# OLM-base_v0_9.net
KiCad netlist of a schematic drawn in EAGLE
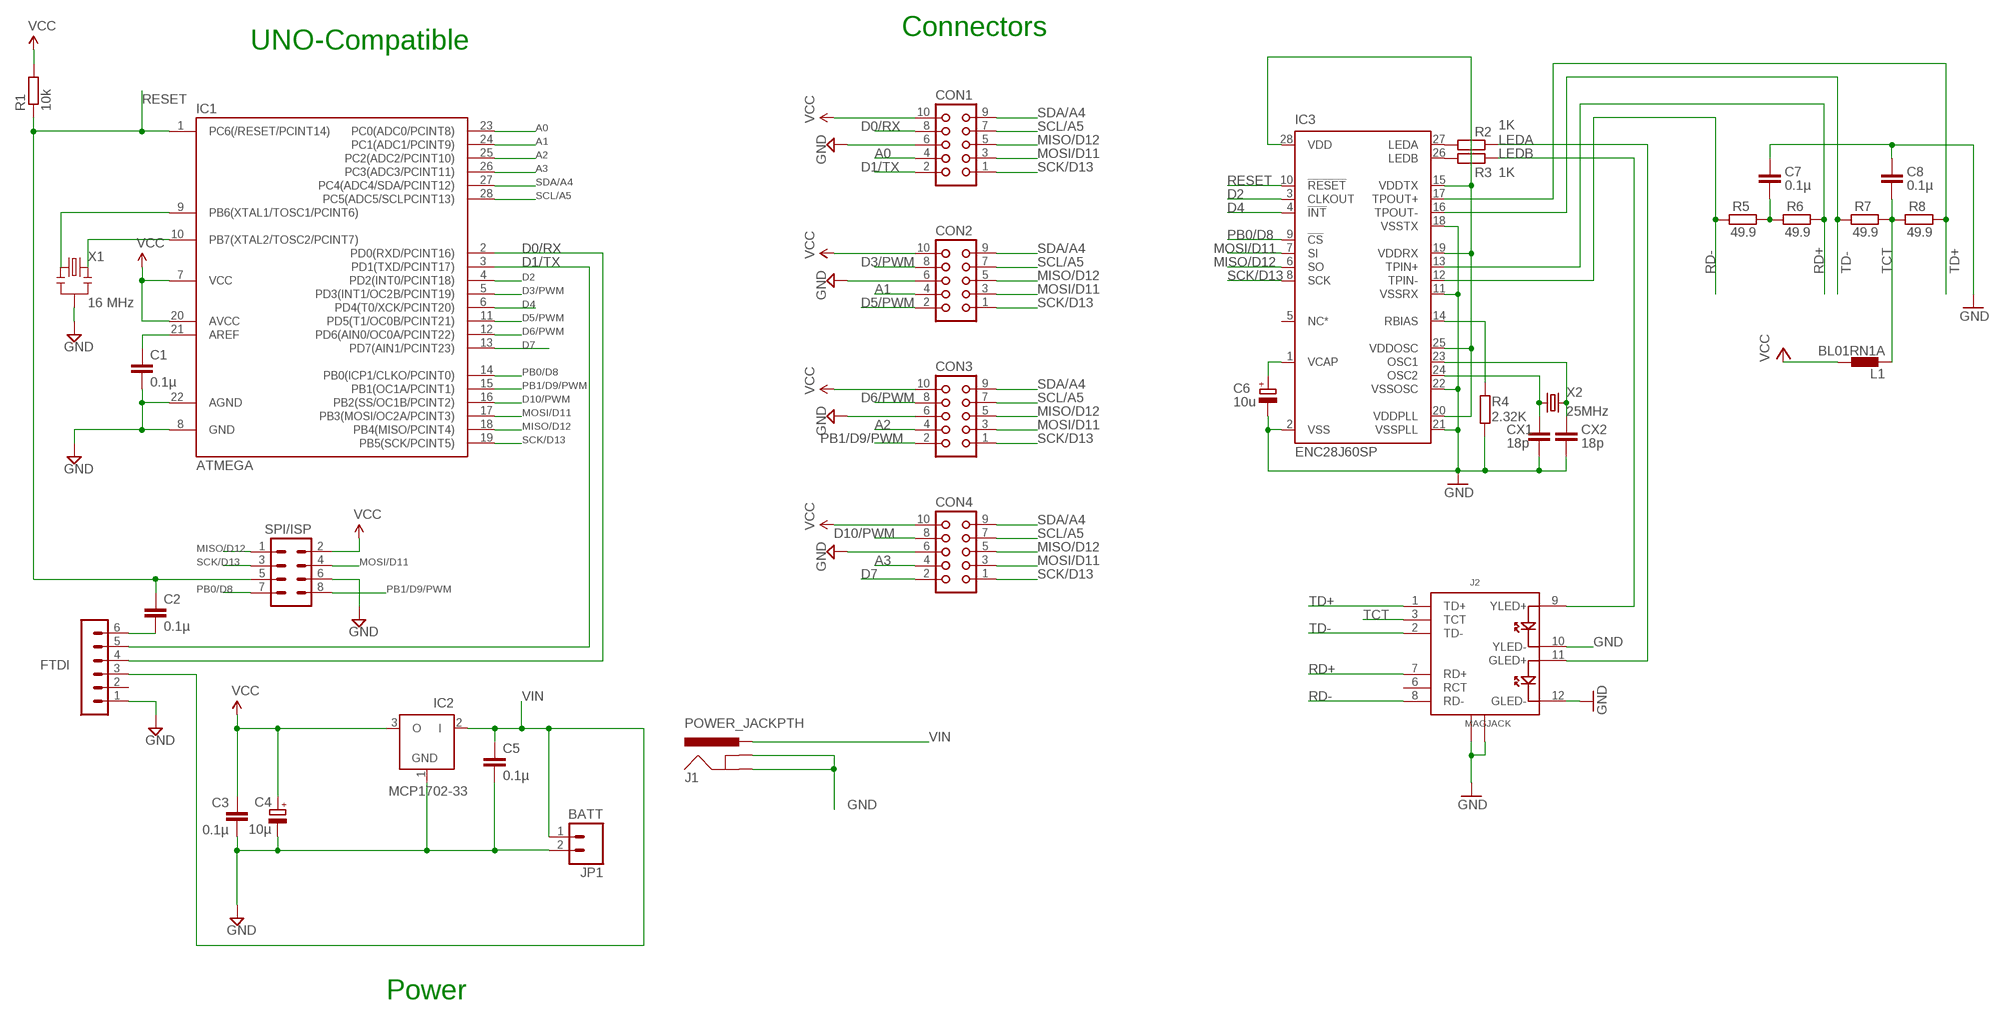
[diagram p0: schematic, sheet 1]

(export (version "E")
  (design (tool "Eeschema 10.0.6"))
  (components
    (comp (ref "C1")
      (value "0.1µ")
      (footprint "eagle-import:C025-024X044")
      (libsource (lib "eagle-import") (part "C-EU025-024X044"))
    )
    (comp (ref "C2")
      (value "0.1µ")
      (footprint "eagle-import:C025-024X044")
      (libsource (lib "eagle-import") (part "C-EU025-024X044"))
    )
    (comp (ref "C3")
      (value "0.1µ")
      (footprint "eagle-import:C025-024X044")
      (libsource (lib "eagle-import") (part "C-EU025-024X044"))
    )
    (comp (ref "C4")
      (value "10µ")
      (footprint "eagle-import:E1,8-4")
      (libsource (lib "eagle-import") (part "CPOL-EUE1.8-4"))
    )
    (comp (ref "C5")
      (value "0.1µ")
      (footprint "eagle-import:C025-024X044")
      (libsource (lib "eagle-import") (part "C-EU025-024X044"))
    )
    (comp (ref "C6")
      (value "10u")
      (footprint "eagle-import:E1,8-4")
      (libsource (lib "eagle-import") (part "CPOL-EUE1.8-4"))
    )
    (comp (ref "C7")
      (value "0.1µ")
      (footprint "eagle-import:C025-024X044")
      (libsource (lib "eagle-import") (part "C-EU025-024X044"))
    )
    (comp (ref "C8")
      (value "0.1µ")
      (footprint "eagle-import:C025-024X044")
      (libsource (lib "eagle-import") (part "C-EU025-024X044"))
    )
    (comp (ref "CON1")
      (value "CON10L")
      (footprint "eagle-import:CON10L")
      (libsource (lib "eagle-import") (part "CON10L"))
    )
    (comp (ref "CON2")
      (value "CON10L")
      (footprint "eagle-import:CON10L")
      (libsource (lib "eagle-import") (part "CON10L"))
    )
    (comp (ref "CON3")
      (value "CON10L")
      (footprint "eagle-import:CON10L")
      (libsource (lib "eagle-import") (part "CON10L"))
    )
    (comp (ref "CON4")
      (value "CON10L")
      (footprint "eagle-import:CON10L")
      (libsource (lib "eagle-import") (part "CON10L"))
    )
    (comp (ref "CX1")
      (value "18p")
      (footprint "eagle-import:C025-024X044")
      (libsource (lib "eagle-import") (part "C-EU025-024X044"))
    )
    (comp (ref "CX2")
      (value "18p")
      (footprint "eagle-import:C025-024X044")
      (libsource (lib "eagle-import") (part "C-EU025-024X044"))
    )
    (comp (ref "FTDI")
      (value "FTDI")
      (footprint "eagle-import:MA06-1")
      (libsource (lib "eagle-import") (part "MA06-1"))
    )
    (comp (ref "IC1")
      (value "ATMEGA")
      (footprint "eagle-import:DIL28-3")
      (libsource (lib "eagle-import") (part "ATMEGA48/88/168-PU"))
    )
    (comp (ref "IC2")
      (value "MCP1702-33")
      (footprint "eagle-import:TO92")
      (libsource (lib "eagle-import") (part "MCP1702Z"))
    )
    (comp (ref "IC3")
      (value "ENC28J60SP")
      (footprint "eagle-import:DIL28-3")
      (fields (field (name "MF") "MICROCHIP") (field (name "MPN") "ENC28J60/SP"))
      (libsource (lib "eagle-import") (part "ENC28J60SP"))
    )
    (comp (ref "J1")
      (value "POWER_JACKPTH")
      (footprint "eagle-import:POWER_JACK_PTH")
      (libsource (lib "eagle-import") (part "POWER_JACKPTH"))
    )
    (comp (ref "J2")
      (value "MAGJACK")
      (footprint "eagle-import:MAGJACK")
      (libsource (lib "eagle-import") (part "MAGJACK"))
    )
    (comp (ref "JP1")
      (value "BATT")
      (footprint "eagle-import:1X02_LOCK_LONGPADS")
      (libsource (lib "eagle-import") (part "M02LOCK_LONGPADS"))
    )
    (comp (ref "L1")
      (value "BL01RN1A")
      (footprint "eagle-import:BL01RN1A")
      (libsource (lib "eagle-import") (part "BL01RN1A"))
    )
    (comp (ref "R1")
      (value "10k")
      (footprint "eagle-import:0204_7")
      (libsource (lib "eagle-import") (part "resistor_R-EU_0204/7"))
    )
    (comp (ref "R2")
      (value "1K")
      (footprint "eagle-import:0204_7")
      (libsource (lib "eagle-import") (part "R-EU_0204/7"))
    )
    (comp (ref "R3")
      (value "1K")
      (footprint "eagle-import:0204_7")
      (libsource (lib "eagle-import") (part "R-EU_0204/7"))
    )
    (comp (ref "R4")
      (value "2.32K")
      (footprint "eagle-import:0204_7")
      (libsource (lib "eagle-import") (part "R-EU_0204/7"))
    )
    (comp (ref "R5")
      (value "49.9")
      (footprint "eagle-import:0204_7")
      (libsource (lib "eagle-import") (part "R-EU_0204/7"))
    )
    (comp (ref "R6")
      (value "49.9")
      (footprint "eagle-import:0204_7")
      (libsource (lib "eagle-import") (part "R-EU_0204/7"))
    )
    (comp (ref "R7")
      (value "49.9")
      (footprint "eagle-import:0204_7")
      (libsource (lib "eagle-import") (part "R-EU_0204/7"))
    )
    (comp (ref "R8")
      (value "49.9")
      (footprint "eagle-import:0204_7")
      (libsource (lib "eagle-import") (part "R-EU_0204/7"))
    )
    (comp (ref "SV1")
      (value "SPI/ISP")
      (footprint "eagle-import:MA04-2")
      (libsource (lib "eagle-import") (part "MA04-2"))
    )
    (comp (ref "X1")
      (value "16 MHz")
      (footprint "eagle-import:RESONATOR-PTH")
      (libsource (lib "eagle-import") (part "RESONATORPTH"))
    )
    (comp (ref "X2")
      (value "25MHz")
      (footprint "eagle-import:HC49US")
      (libsource (lib "eagle-import") (part "CRYSTALHC49US"))
    )
  )
  (nets
    (net (code "1") (name "/A0") (class "Default")
      (node (ref "CON1") (pin "4") (pinfunction "4_4") (pintype "passive"))
      (node (ref "IC1") (pin "23") (pinfunction "PC0(ADC0/PCINT8)_23") (pintype "bidirectional"))
    )
    (net (code "2") (name "/A1") (class "Default")
      (node (ref "CON2") (pin "4") (pinfunction "4_4") (pintype "passive"))
      (node (ref "IC1") (pin "24") (pinfunction "PC1(ADC1/PCINT9)_24") (pintype "bidirectional"))
    )
    (net (code "3") (name "/A2") (class "Default")
      (node (ref "CON3") (pin "4") (pinfunction "4_4") (pintype "passive"))
      (node (ref "IC1") (pin "25") (pinfunction "PC2(ADC2/PCINT10)_25") (pintype "bidirectional"))
    )
    (net (code "4") (name "/A3") (class "Default")
      (node (ref "CON4") (pin "4") (pinfunction "4_4") (pintype "passive"))
      (node (ref "IC1") (pin "26") (pinfunction "PC3(ADC3/PCINT11)_26") (pintype "bidirectional"))
    )
    (net (code "5") (name "/D0{slash}RX") (class "Default")
      (node (ref "CON1") (pin "8") (pinfunction "8_8") (pintype "passive"))
      (node (ref "FTDI") (pin "4") (pinfunction "4_4") (pintype "passive"))
      (node (ref "IC1") (pin "2") (pinfunction "PD0(RXD/PCINT16)_2") (pintype "bidirectional"))
    )
    (net (code "6") (name "/D1{slash}TX") (class "Default")
      (node (ref "CON1") (pin "2") (pinfunction "2_2") (pintype "passive"))
      (node (ref "FTDI") (pin "5") (pinfunction "5_5") (pintype "passive"))
      (node (ref "IC1") (pin "3") (pinfunction "PD1(TXD/PCINT17)_3") (pintype "bidirectional"))
    )
    (net (code "7") (name "/D2") (class "Default")
      (node (ref "IC1") (pin "4") (pinfunction "PD2(INT0/PCINT18)_4") (pintype "bidirectional"))
      (node (ref "IC3") (pin "3") (pinfunction "CLKOUT_3") (pintype "output"))
    )
    (net (code "8") (name "/D3{slash}PWM") (class "Default")
      (node (ref "CON2") (pin "8") (pinfunction "8_8") (pintype "passive"))
      (node (ref "IC1") (pin "5") (pinfunction "PD3(INT1/OC2B/PCINT19)_5") (pintype "bidirectional"))
    )
    (net (code "9") (name "/D4") (class "Default")
      (node (ref "IC1") (pin "6") (pinfunction "PD4(T0/XCK/PCINT20)_6") (pintype "bidirectional"))
      (node (ref "IC3") (pin "4") (pinfunction "~{INT}_4") (pintype "output"))
    )
    (net (code "10") (name "/D5{slash}PWM") (class "Default")
      (node (ref "CON2") (pin "2") (pinfunction "2_2") (pintype "passive"))
      (node (ref "IC1") (pin "11") (pinfunction "PD5(T1/OC0B/PCINT21)_11") (pintype "bidirectional"))
    )
    (net (code "11") (name "/D6{slash}PWM") (class "Default")
      (node (ref "CON3") (pin "8") (pinfunction "8_8") (pintype "passive"))
      (node (ref "IC1") (pin "12") (pinfunction "PD6(AIN0/OC0A/PCINT22)_12") (pintype "bidirectional"))
    )
    (net (code "12") (name "/D7") (class "Default")
      (node (ref "CON4") (pin "2") (pinfunction "2_2") (pintype "passive"))
      (node (ref "IC1") (pin "13") (pinfunction "PD7(AIN1/PCINT23)_13") (pintype "bidirectional"))
    )
    (net (code "13") (name "/D10{slash}PWM") (class "Default")
      (node (ref "CON4") (pin "8") (pinfunction "8_8") (pintype "passive"))
      (node (ref "IC1") (pin "16") (pinfunction "PB2(SS/OC1B/PCINT2)_16") (pintype "bidirectional"))
    )
    (net (code "14") (name "/LEDA") (class "Default")
      (node (ref "J2") (pin "11") (pinfunction "GLED+_11") (pintype "bidirectional"))
      (node (ref "R2") (pin "2") (pinfunction "2_2") (pintype "passive"))
    )
    (net (code "15") (name "/LEDB") (class "Default")
      (node (ref "J2") (pin "9") (pinfunction "YLED+_9") (pintype "bidirectional"))
      (node (ref "R3") (pin "2") (pinfunction "2_2") (pintype "passive"))
    )
    (net (code "16") (name "/MISO{slash}D12") (class "Default")
      (node (ref "CON1") (pin "5") (pinfunction "5_5") (pintype "passive"))
      (node (ref "CON2") (pin "5") (pinfunction "5_5") (pintype "passive"))
      (node (ref "CON3") (pin "5") (pinfunction "5_5") (pintype "passive"))
      (node (ref "CON4") (pin "5") (pinfunction "5_5") (pintype "passive"))
      (node (ref "IC1") (pin "18") (pinfunction "PB4(MISO/PCINT4)_18") (pintype "bidirectional"))
      (node (ref "IC3") (pin "6") (pinfunction "SO_6") (pintype "output"))
      (node (ref "SV1") (pin "1") (pinfunction "1_1") (pintype "passive"))
    )
    (net (code "17") (name "/MOSI{slash}D11") (class "Default")
      (node (ref "CON1") (pin "3") (pinfunction "3_3") (pintype "passive"))
      (node (ref "CON2") (pin "3") (pinfunction "3_3") (pintype "passive"))
      (node (ref "CON3") (pin "3") (pinfunction "3_3") (pintype "passive"))
      (node (ref "CON4") (pin "3") (pinfunction "3_3") (pintype "passive"))
      (node (ref "IC1") (pin "17") (pinfunction "PB3(MOSI/OC2A/PCINT3)_17") (pintype "bidirectional"))
      (node (ref "IC3") (pin "7") (pinfunction "SI_7") (pintype "input"))
      (node (ref "SV1") (pin "4") (pinfunction "4_4") (pintype "passive"))
    )
    (net (code "18") (name "/PB0{slash}D8") (class "Default")
      (node (ref "IC1") (pin "14") (pinfunction "PB0(ICP1/CLKO/PCINT0)_14") (pintype "bidirectional"))
      (node (ref "IC3") (pin "9") (pinfunction "~{CS}_9") (pintype "input"))
      (node (ref "SV1") (pin "7") (pinfunction "7_7") (pintype "passive"))
    )
    (net (code "19") (name "/PB1{slash}D9{slash}PWM") (class "Default")
      (node (ref "CON3") (pin "2") (pinfunction "2_2") (pintype "passive"))
      (node (ref "IC1") (pin "15") (pinfunction "PB1(OC1A/PCINT1)_15") (pintype "bidirectional"))
      (node (ref "SV1") (pin "8") (pinfunction "8_8") (pintype "passive"))
    )
    (net (code "20") (name "/RD+") (class "Default")
      (node (ref "IC3") (pin "13") (pinfunction "TPIN+_13") (pintype "input"))
      (node (ref "J2") (pin "7") (pinfunction "RD+_7") (pintype "bidirectional"))
      (node (ref "R6") (pin "2") (pinfunction "2_2") (pintype "passive"))
    )
    (net (code "21") (name "/RD-") (class "Default")
      (node (ref "IC3") (pin "12") (pinfunction "TPIN-_12") (pintype "input"))
      (node (ref "J2") (pin "8") (pinfunction "RD-_8") (pintype "bidirectional"))
      (node (ref "R5") (pin "1") (pinfunction "1_1") (pintype "passive"))
    )
    (net (code "22") (name "/RESET") (class "Default")
      (node (ref "C2") (pin "1") (pinfunction "1_1") (pintype "passive"))
      (node (ref "IC1") (pin "1") (pinfunction "PC6(/RESET/PCINT14)_1") (pintype "bidirectional"))
      (node (ref "IC3") (pin "10") (pinfunction "~{RESET}_10") (pintype "input"))
      (node (ref "R1") (pin "1") (pinfunction "1_1") (pintype "passive"))
      (node (ref "SV1") (pin "5") (pinfunction "5_5") (pintype "passive"))
    )
    (net (code "23") (name "/SCK{slash}D13") (class "Default")
      (node (ref "CON1") (pin "1") (pinfunction "1_1") (pintype "passive"))
      (node (ref "CON2") (pin "1") (pinfunction "1_1") (pintype "passive"))
      (node (ref "CON3") (pin "1") (pinfunction "1_1") (pintype "passive"))
      (node (ref "CON4") (pin "1") (pinfunction "1_1") (pintype "passive"))
      (node (ref "IC1") (pin "19") (pinfunction "PB5(SCK/PCINT5)_19") (pintype "bidirectional"))
      (node (ref "IC3") (pin "8") (pinfunction "SCK_8") (pintype "input"))
      (node (ref "SV1") (pin "3") (pinfunction "3_3") (pintype "passive"))
    )
    (net (code "24") (name "/SCL{slash}A5") (class "Default")
      (node (ref "CON1") (pin "7") (pinfunction "7_7") (pintype "passive"))
      (node (ref "CON2") (pin "7") (pinfunction "7_7") (pintype "passive"))
      (node (ref "CON3") (pin "7") (pinfunction "7_7") (pintype "passive"))
      (node (ref "CON4") (pin "7") (pinfunction "7_7") (pintype "passive"))
      (node (ref "IC1") (pin "28") (pinfunction "PC5(ADC5/SCLPCINT13)_28") (pintype "bidirectional"))
    )
    (net (code "25") (name "/SDA{slash}A4") (class "Default")
      (node (ref "CON1") (pin "9") (pinfunction "9_9") (pintype "passive"))
      (node (ref "CON2") (pin "9") (pinfunction "9_9") (pintype "passive"))
      (node (ref "CON3") (pin "9") (pinfunction "9_9") (pintype "passive"))
      (node (ref "CON4") (pin "9") (pinfunction "9_9") (pintype "passive"))
      (node (ref "IC1") (pin "27") (pinfunction "PC4(ADC4/SDA/PCINT12)_27") (pintype "bidirectional"))
    )
    (net (code "26") (name "/TCT") (class "Default")
      (node (ref "C8") (pin "2") (pinfunction "2_2") (pintype "passive"))
      (node (ref "J2") (pin "3") (pinfunction "TCT_3") (pintype "bidirectional"))
      (node (ref "L1") (pin "1") (pinfunction "1_1") (pintype "passive"))
      (node (ref "R7") (pin "2") (pinfunction "2_2") (pintype "passive"))
      (node (ref "R8") (pin "1") (pinfunction "1_1") (pintype "passive"))
    )
    (net (code "27") (name "/TD+") (class "Default")
      (node (ref "IC3") (pin "17") (pinfunction "TPOUT+_17") (pintype "output"))
      (node (ref "J2") (pin "1") (pinfunction "TD+_1") (pintype "bidirectional"))
      (node (ref "R8") (pin "2") (pinfunction "2_2") (pintype "passive"))
    )
    (net (code "28") (name "/TD-") (class "Default")
      (node (ref "IC3") (pin "16") (pinfunction "TPOUT-_16") (pintype "output"))
      (node (ref "J2") (pin "2") (pinfunction "TD-_2") (pintype "bidirectional"))
      (node (ref "R7") (pin "1") (pinfunction "1_1") (pintype "passive"))
    )
    (net (code "29") (name "/VIN") (class "Default")
      (node (ref "C5") (pin "1") (pinfunction "1_1") (pintype "passive"))
      (node (ref "FTDI") (pin "3") (pinfunction "3_3") (pintype "passive"))
      (node (ref "IC2") (pin "2") (pinfunction "I_2") (pintype "input"))
      (node (ref "J1") (pin "PWR") (pinfunction "PWR_PWR") (pintype "bidirectional"))
      (node (ref "JP1") (pin "1") (pinfunction "1_1") (pintype "passive"))
    )
    (net (code "30") (name "GND") (class "Default")
      (node (ref "C1") (pin "2") (pinfunction "2_2") (pintype "passive"))
      (node (ref "C3") (pin "2") (pinfunction "2_2") (pintype "passive"))
      (node (ref "C4") (pin "-") (pinfunction "-_-") (pintype "passive"))
      (node (ref "C5") (pin "2") (pinfunction "2_2") (pintype "passive"))
      (node (ref "C6") (pin "-") (pinfunction "-_-") (pintype "passive"))
      (node (ref "C7") (pin "1") (pinfunction "1_1") (pintype "passive"))
      (node (ref "C8") (pin "1") (pinfunction "1_1") (pintype "passive"))
      (node (ref "CON1") (pin "6") (pinfunction "6_6") (pintype "passive"))
      (node (ref "CON2") (pin "6") (pinfunction "6_6") (pintype "passive"))
      (node (ref "CON3") (pin "6") (pinfunction "6_6") (pintype "passive"))
      (node (ref "CON4") (pin "6") (pinfunction "6_6") (pintype "passive"))
      (node (ref "CX1") (pin "2") (pinfunction "2_2") (pintype "passive"))
      (node (ref "CX2") (pin "2") (pinfunction "2_2") (pintype "passive"))
      (node (ref "FTDI") (pin "1") (pinfunction "1_1") (pintype "passive"))
      (node (ref "IC1") (pin "22") (pinfunction "AGND_22") (pintype "power_in"))
      (node (ref "IC1") (pin "8") (pinfunction "GND_8") (pintype "power_in"))
      (node (ref "IC2") (pin "1") (pinfunction "GND_1") (pintype "power_in"))
      (node (ref "IC3") (pin "11") (pinfunction "VSSRX_11") (pintype "input"))
      (node (ref "IC3") (pin "18") (pinfunction "VSSTX_18") (pintype "input"))
      (node (ref "IC3") (pin "2") (pinfunction "VSS_2") (pintype "input"))
      (node (ref "IC3") (pin "21") (pinfunction "VSSPLL_21") (pintype "input"))
      (node (ref "IC3") (pin "22") (pinfunction "VSSOSC_22") (pintype "input"))
      (node (ref "J1") (pin "GND") (pinfunction "GND_GND") (pintype "bidirectional"))
      (node (ref "J1") (pin "GNDBREAK") (pinfunction "GNDBREAK_GNDBREAK") (pintype "bidirectional"))
      (node (ref "J2") (pin "10") (pinfunction "YLED-_10") (pintype "bidirectional"))
      (node (ref "J2") (pin "12") (pinfunction "GLED-_12") (pintype "bidirectional"))
      (node (ref "J2") (pin "M1") (pinfunction "GND1_M1") (pintype "bidirectional"))
      (node (ref "J2") (pin "M2") (pinfunction "GND2_M2") (pintype "bidirectional"))
      (node (ref "JP1") (pin "2") (pinfunction "2_2") (pintype "passive"))
      (node (ref "R4") (pin "2") (pinfunction "2_2") (pintype "passive"))
      (node (ref "SV1") (pin "6") (pinfunction "6_6") (pintype "passive"))
      (node (ref "X1") (pin "2") (pinfunction "2_2") (pintype "passive"))
    )
    (net (code "31") (name "Net-(C2-Pad2)") (class "Default")
      (node (ref "C2") (pin "2") (pinfunction "2_2") (pintype "passive"))
      (node (ref "FTDI") (pin "6") (pinfunction "6_6") (pintype "passive"))
    )
    (net (code "32") (name "Net-(C7-Pad2)") (class "Default")
      (node (ref "C7") (pin "2") (pinfunction "2_2") (pintype "passive"))
      (node (ref "R5") (pin "2") (pinfunction "2_2") (pintype "passive"))
      (node (ref "R6") (pin "1") (pinfunction "1_1") (pintype "passive"))
    )
    (net (code "33") (name "Net-(IC1-AREF)") (class "Default")
      (node (ref "C1") (pin "1") (pinfunction "1_1") (pintype "passive"))
      (node (ref "IC1") (pin "21") (pinfunction "AREF_21") (pintype "passive"))
    )
    (net (code "34") (name "Net-(IC1-PB6(XTAL1{slash}TOSC1{slash}PCINT6))") (class "Default")
      (node (ref "IC1") (pin "9") (pinfunction "PB6(XTAL1/TOSC1/PCINT6)_9") (pintype "bidirectional"))
      (node (ref "X1") (pin "1") (pinfunction "1_1") (pintype "passive"))
    )
    (net (code "35") (name "Net-(IC1-PB7(XTAL2{slash}TOSC2{slash}PCINT7))") (class "Default")
      (node (ref "IC1") (pin "10") (pinfunction "PB7(XTAL2/TOSC2/PCINT7)_10") (pintype "bidirectional"))
      (node (ref "X1") (pin "3") (pinfunction "3_3") (pintype "passive"))
    )
    (net (code "36") (name "Net-(IC3-LEDA)") (class "Default")
      (node (ref "IC3") (pin "27") (pinfunction "LEDA_27") (pintype "output"))
      (node (ref "R2") (pin "1") (pinfunction "1_1") (pintype "passive"))
    )
    (net (code "37") (name "Net-(IC3-LEDB)") (class "Default")
      (node (ref "IC3") (pin "26") (pinfunction "LEDB_26") (pintype "output"))
      (node (ref "R3") (pin "1") (pinfunction "1_1") (pintype "passive"))
    )
    (net (code "38") (name "Net-(IC3-OSC1)") (class "Default")
      (node (ref "CX2") (pin "1") (pinfunction "1_1") (pintype "passive"))
      (node (ref "IC3") (pin "23") (pinfunction "OSC1_23") (pintype "input"))
      (node (ref "X2") (pin "2") (pinfunction "2_2") (pintype "passive"))
    )
    (net (code "39") (name "Net-(IC3-OSC2)") (class "Default")
      (node (ref "CX1") (pin "1") (pinfunction "1_1") (pintype "passive"))
      (node (ref "IC3") (pin "24") (pinfunction "OSC2_24") (pintype "output"))
      (node (ref "X2") (pin "1") (pinfunction "1_1") (pintype "passive"))
    )
    (net (code "40") (name "Net-(IC3-RBIAS)") (class "Default")
      (node (ref "IC3") (pin "14") (pinfunction "RBIAS_14") (pintype "input"))
      (node (ref "R4") (pin "1") (pinfunction "1_1") (pintype "passive"))
    )
    (net (code "41") (name "Net-(IC3-VCAP)") (class "Default")
      (node (ref "C6") (pin "+") (pinfunction "+_+") (pintype "passive"))
      (node (ref "IC3") (pin "1") (pinfunction "VCAP_1") (pintype "input"))
    )
    (net (code "42") (name "VCC") (class "Default")
      (node (ref "C3") (pin "1") (pinfunction "1_1") (pintype "passive"))
      (node (ref "C4") (pin "+") (pinfunction "+_+") (pintype "passive"))
      (node (ref "CON1") (pin "10") (pinfunction "10_10") (pintype "passive"))
      (node (ref "CON2") (pin "10") (pinfunction "10_10") (pintype "passive"))
      (node (ref "CON3") (pin "10") (pinfunction "10_10") (pintype "passive"))
      (node (ref "CON4") (pin "10") (pinfunction "10_10") (pintype "passive"))
      (node (ref "IC1") (pin "20") (pinfunction "AVCC_20") (pintype "passive"))
      (node (ref "IC1") (pin "7") (pinfunction "VCC_7") (pintype "power_in"))
      (node (ref "IC2") (pin "3") (pinfunction "O_3") (pintype "input"))
      (node (ref "IC3") (pin "15") (pinfunction "VDDTX_15") (pintype "input"))
      (node (ref "IC3") (pin "19") (pinfunction "VDDRX_19") (pintype "input"))
      (node (ref "IC3") (pin "20") (pinfunction "VDDPLL_20") (pintype "input"))
      (node (ref "IC3") (pin "25") (pinfunction "VDDOSC_25") (pintype "input"))
      (node (ref "IC3") (pin "28") (pinfunction "VDD_28") (pintype "input"))
      (node (ref "L1") (pin "2") (pinfunction "2_2") (pintype "passive"))
      (node (ref "R1") (pin "2") (pinfunction "2_2") (pintype "passive"))
      (node (ref "SV1") (pin "2") (pinfunction "2_2") (pintype "passive"))
    )
    (net (code "43") (name "unconnected-(FTDI-Pad2)") (class "Default")
      (node (ref "FTDI") (pin "2") (pinfunction "2_2") (pintype "passive"))
    )
    (net (code "44") (name "unconnected-(IC3-NC*-Pad5)") (class "Default")
      (node (ref "IC3") (pin "5") (pinfunction "NC*_5") (pintype "output"))
    )
    (net (code "45") (name "unconnected-(J2-RCT-Pad6)") (class "Default")
      (node (ref "J2") (pin "6") (pinfunction "RCT_6") (pintype "bidirectional"))
    )
  )
)
